# sensor_t.net
KiCad netlist of a schematic drawn in EAGLE
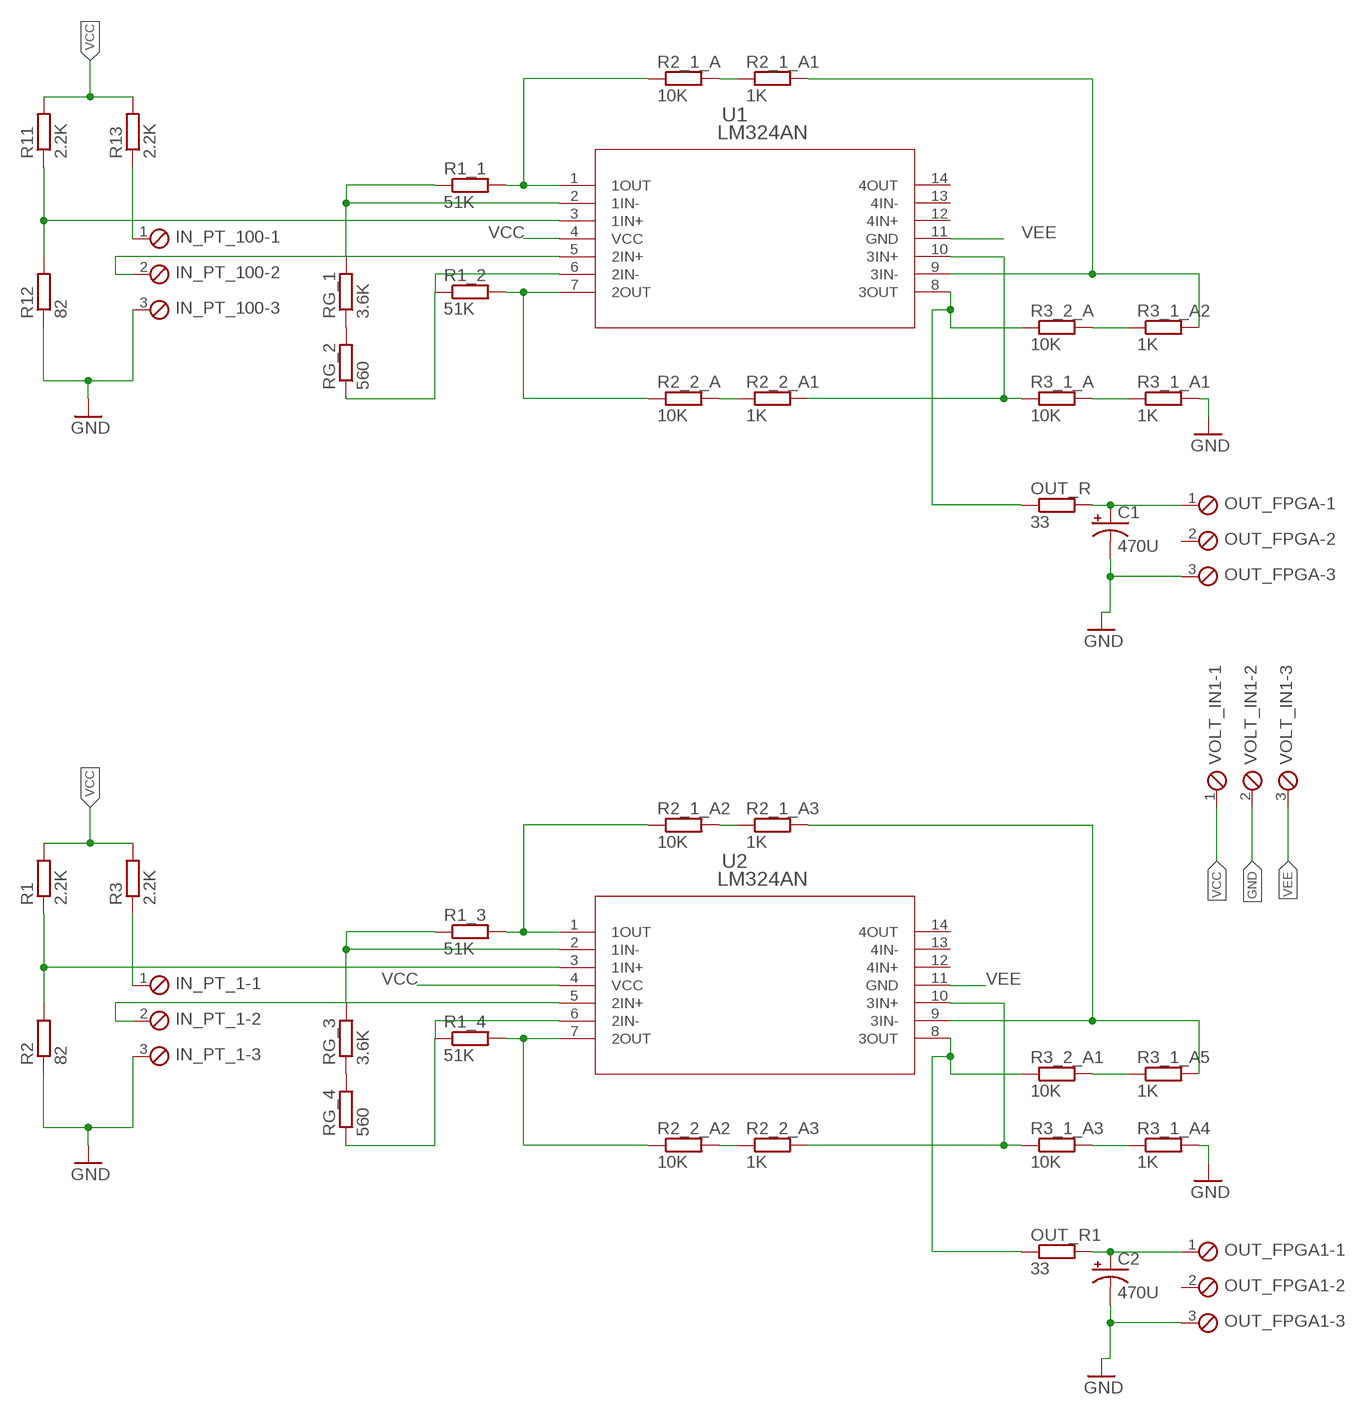
[diagram p0: schematic, sheet 1]

(export (version "E")
  (design (tool "Eeschema 10.0.6"))
  (components
    (comp (ref "C1")
      (value "470U")
      (footprint "eagle-import:TAP5-80")
      (libsource (lib "eagle-import") (part "CPOL-USTAP5-80"))
    )
    (comp (ref "C2")
      (value "470U")
      (footprint "eagle-import:TAP5-80")
      (libsource (lib "eagle-import") (part "CPOL-USTAP5-80"))
    )
    (comp (ref "IN_PT_1")
      (value "MPT3")
      (footprint "eagle-import:3POL254")
      (libsource (lib "eagle-import") (part "MPT3"))
    )
    (comp (ref "IN_PT_100")
      (value "MPT3")
      (footprint "eagle-import:3POL254")
      (libsource (lib "eagle-import") (part "MPT3"))
    )
    (comp (ref "OUT_FPGA")
      (value "MPT3")
      (footprint "eagle-import:3POL254")
      (libsource (lib "eagle-import") (part "MPT3"))
    )
    (comp (ref "OUT_FPGA1")
      (value "MPT3")
      (footprint "eagle-import:3POL254")
      (libsource (lib "eagle-import") (part "MPT3"))
    )
    (comp (ref "OUT_R")
      (value "33")
      (footprint "eagle-import:0207_10")
      (libsource (lib "eagle-import") (part "R-EU_0207/10"))
    )
    (comp (ref "OUT_R1")
      (value "33")
      (footprint "eagle-import:0207_10")
      (libsource (lib "eagle-import") (part "R-EU_0207/10"))
    )
    (comp (ref "R1")
      (value "2.2K")
      (footprint "eagle-import:0207_10")
      (libsource (lib "eagle-import") (part "R-EU_0207/10"))
    )
    (comp (ref "R1_1")
      (value "51K")
      (footprint "eagle-import:0207_10")
      (libsource (lib "eagle-import") (part "R-EU_0207/10"))
    )
    (comp (ref "R1_2")
      (value "51K")
      (footprint "eagle-import:0207_10")
      (libsource (lib "eagle-import") (part "R-EU_0207/10"))
    )
    (comp (ref "R1_3")
      (value "51K")
      (footprint "eagle-import:0207_10")
      (libsource (lib "eagle-import") (part "R-EU_0207/10"))
    )
    (comp (ref "R1_4")
      (value "51K")
      (footprint "eagle-import:0207_10")
      (libsource (lib "eagle-import") (part "R-EU_0207/10"))
    )
    (comp (ref "R2")
      (value "82")
      (footprint "eagle-import:0207_10")
      (libsource (lib "eagle-import") (part "R-EU_0207/10"))
    )
    (comp (ref "R2_1_A")
      (value "10K")
      (footprint "eagle-import:0207_10")
      (libsource (lib "eagle-import") (part "R-EU_0207/10"))
    )
    (comp (ref "R2_1_A1")
      (value "1K")
      (footprint "eagle-import:0207_10")
      (libsource (lib "eagle-import") (part "R-EU_0207/10"))
    )
    (comp (ref "R2_1_A2")
      (value "10K")
      (footprint "eagle-import:0207_10")
      (libsource (lib "eagle-import") (part "R-EU_0207/10"))
    )
    (comp (ref "R2_1_A3")
      (value "1K")
      (footprint "eagle-import:0207_10")
      (libsource (lib "eagle-import") (part "R-EU_0207/10"))
    )
    (comp (ref "R2_2_A")
      (value "10K")
      (footprint "eagle-import:0207_10")
      (libsource (lib "eagle-import") (part "R-EU_0207/10"))
    )
    (comp (ref "R2_2_A1")
      (value "1K")
      (footprint "eagle-import:0207_10")
      (libsource (lib "eagle-import") (part "R-EU_0207/10"))
    )
    (comp (ref "R2_2_A2")
      (value "10K")
      (footprint "eagle-import:0207_10")
      (libsource (lib "eagle-import") (part "R-EU_0207/10"))
    )
    (comp (ref "R2_2_A3")
      (value "1K")
      (footprint "eagle-import:0207_10")
      (libsource (lib "eagle-import") (part "R-EU_0207/10"))
    )
    (comp (ref "R3")
      (value "2.2K")
      (footprint "eagle-import:0207_10")
      (libsource (lib "eagle-import") (part "R-EU_0207/10"))
    )
    (comp (ref "R3_1_A")
      (value "10K")
      (footprint "eagle-import:0207_10")
      (libsource (lib "eagle-import") (part "R-EU_0207/10"))
    )
    (comp (ref "R3_1_A1")
      (value "1K")
      (footprint "eagle-import:0207_10")
      (libsource (lib "eagle-import") (part "R-EU_0207/10"))
    )
    (comp (ref "R3_1_A2")
      (value "1K")
      (footprint "eagle-import:0207_10")
      (libsource (lib "eagle-import") (part "R-EU_0207/10"))
    )
    (comp (ref "R3_1_A3")
      (value "10K")
      (footprint "eagle-import:0207_10")
      (libsource (lib "eagle-import") (part "R-EU_0207/10"))
    )
    (comp (ref "R3_1_A4")
      (value "1K")
      (footprint "eagle-import:0207_10")
      (libsource (lib "eagle-import") (part "R-EU_0207/10"))
    )
    (comp (ref "R3_1_A5")
      (value "1K")
      (footprint "eagle-import:0207_10")
      (libsource (lib "eagle-import") (part "R-EU_0207/10"))
    )
    (comp (ref "R3_2_A")
      (value "10K")
      (footprint "eagle-import:0207_10")
      (libsource (lib "eagle-import") (part "R-EU_0207/10"))
    )
    (comp (ref "R3_2_A1")
      (value "10K")
      (footprint "eagle-import:0207_10")
      (libsource (lib "eagle-import") (part "R-EU_0207/10"))
    )
    (comp (ref "R11")
      (value "2.2K")
      (footprint "eagle-import:0207_10")
      (libsource (lib "eagle-import") (part "R-EU_0207/10"))
    )
    (comp (ref "R12")
      (value "82")
      (footprint "eagle-import:0207_10")
      (libsource (lib "eagle-import") (part "R-EU_0207/10"))
    )
    (comp (ref "R13")
      (value "2.2K")
      (footprint "eagle-import:0207_10")
      (libsource (lib "eagle-import") (part "R-EU_0207/10"))
    )
    (comp (ref "RG_1")
      (value "3.6K")
      (footprint "eagle-import:0207_10")
      (libsource (lib "eagle-import") (part "R-EU_0207/10"))
    )
    (comp (ref "RG_2")
      (value "560")
      (footprint "eagle-import:0207_10")
      (libsource (lib "eagle-import") (part "R-EU_0207/10"))
    )
    (comp (ref "RG_3")
      (value "3.6K")
      (footprint "eagle-import:0207_10")
      (libsource (lib "eagle-import") (part "R-EU_0207/10"))
    )
    (comp (ref "RG_4")
      (value "560")
      (footprint "eagle-import:0207_10")
      (libsource (lib "eagle-import") (part "R-EU_0207/10"))
    )
    (comp (ref "U1")
      (value "LM324AN")
      (footprint "eagle-import:N14")
      (fields (field (name "COPYRIGHT") "Copyright (C) 2023 Ultra Librarian. All rights reserved."))
      (libsource (lib "eagle-import") (part "LM324AN"))
    )
    (comp (ref "U2")
      (value "LM324AN")
      (footprint "eagle-import:N14")
      (fields (field (name "COPYRIGHT") "Copyright (C) 2023 Ultra Librarian. All rights reserved."))
      (libsource (lib "eagle-import") (part "LM324AN"))
    )
    (comp (ref "VOLT_IN1")
      (value "MPT3")
      (footprint "eagle-import:3POL254")
      (libsource (lib "eagle-import") (part "MPT3"))
    )
  )
  (nets
    (net (code "1") (name "GND") (class "Default")
      (node (ref "C1") (pin "-") (pinfunction "-_-") (pintype "passive"))
      (node (ref "C2") (pin "-") (pinfunction "-_-") (pintype "passive"))
      (node (ref "IN_PT_1") (pin "3") (pinfunction "1_3") (pintype "passive"))
      (node (ref "IN_PT_100") (pin "3") (pinfunction "1_3") (pintype "passive"))
      (node (ref "OUT_FPGA") (pin "3") (pinfunction "1_3") (pintype "passive"))
      (node (ref "OUT_FPGA1") (pin "3") (pinfunction "1_3") (pintype "passive"))
      (node (ref "R12") (pin "1") (pinfunction "1_1") (pintype "passive"))
      (node (ref "R2") (pin "1") (pinfunction "1_1") (pintype "passive"))
      (node (ref "R3_1_A1") (pin "2") (pinfunction "2_2") (pintype "passive"))
      (node (ref "R3_1_A4") (pin "2") (pinfunction "2_2") (pintype "passive"))
      (node (ref "VOLT_IN1") (pin "2") (pinfunction "1_2") (pintype "passive"))
    )
    (net (code "2") (name "Net-(C1-Pad+)") (class "Default")
      (node (ref "C1") (pin "+") (pinfunction "+_+") (pintype "passive"))
      (node (ref "OUT_FPGA") (pin "1") (pinfunction "1_1") (pintype "passive"))
      (node (ref "OUT_R") (pin "2") (pinfunction "2_2") (pintype "passive"))
    )
    (net (code "3") (name "Net-(C2-Pad+)") (class "Default")
      (node (ref "C2") (pin "+") (pinfunction "+_+") (pintype "passive"))
      (node (ref "OUT_FPGA1") (pin "1") (pinfunction "1_1") (pintype "passive"))
      (node (ref "OUT_R1") (pin "2") (pinfunction "2_2") (pintype "passive"))
    )
    (net (code "4") (name "Net-(IN_PT_1-Pad1)") (class "Default")
      (node (ref "IN_PT_1") (pin "1") (pinfunction "1_1") (pintype "passive"))
      (node (ref "R3") (pin "1") (pinfunction "1_1") (pintype "passive"))
    )
    (net (code "5") (name "Net-(IN_PT_1B-1)") (class "Default")
      (node (ref "IN_PT_1") (pin "2") (pinfunction "1_2") (pintype "passive"))
      (node (ref "U2") (pin "5") (pinfunction "2IN+_5") (pintype "input"))
    )
    (net (code "6") (name "Net-(IN_PT_100-Pad1)") (class "Default")
      (node (ref "IN_PT_100") (pin "1") (pinfunction "1_1") (pintype "passive"))
      (node (ref "R13") (pin "1") (pinfunction "1_1") (pintype "passive"))
    )
    (net (code "7") (name "Net-(IN_PT_100B-1)") (class "Default")
      (node (ref "IN_PT_100") (pin "2") (pinfunction "1_2") (pintype "passive"))
      (node (ref "U1") (pin "5") (pinfunction "2IN+_5") (pintype "input"))
    )
    (net (code "8") (name "Net-(R2_1_A-Pad2)") (class "Default")
      (node (ref "R2_1_A") (pin "2") (pinfunction "2_2") (pintype "passive"))
      (node (ref "R2_1_A1") (pin "1") (pinfunction "1_1") (pintype "passive"))
    )
    (net (code "9") (name "Net-(R2_1_A2-Pad2)") (class "Default")
      (node (ref "R2_1_A2") (pin "2") (pinfunction "2_2") (pintype "passive"))
      (node (ref "R2_1_A3") (pin "1") (pinfunction "1_1") (pintype "passive"))
    )
    (net (code "10") (name "Net-(R2_2_A-Pad2)") (class "Default")
      (node (ref "R2_2_A") (pin "2") (pinfunction "2_2") (pintype "passive"))
      (node (ref "R2_2_A1") (pin "1") (pinfunction "1_1") (pintype "passive"))
    )
    (net (code "11") (name "Net-(R2_2_A2-Pad2)") (class "Default")
      (node (ref "R2_2_A2") (pin "2") (pinfunction "2_2") (pintype "passive"))
      (node (ref "R2_2_A3") (pin "1") (pinfunction "1_1") (pintype "passive"))
    )
    (net (code "12") (name "Net-(R3_1_A-Pad2)") (class "Default")
      (node (ref "R3_1_A") (pin "2") (pinfunction "2_2") (pintype "passive"))
      (node (ref "R3_1_A1") (pin "1") (pinfunction "1_1") (pintype "passive"))
    )
    (net (code "13") (name "Net-(R3_1_A2-Pad1)") (class "Default")
      (node (ref "R3_1_A2") (pin "1") (pinfunction "1_1") (pintype "passive"))
      (node (ref "R3_2_A") (pin "2") (pinfunction "2_2") (pintype "passive"))
    )
    (net (code "14") (name "Net-(R3_1_A3-Pad2)") (class "Default")
      (node (ref "R3_1_A3") (pin "2") (pinfunction "2_2") (pintype "passive"))
      (node (ref "R3_1_A4") (pin "1") (pinfunction "1_1") (pintype "passive"))
    )
    (net (code "15") (name "Net-(R3_1_A5-Pad1)") (class "Default")
      (node (ref "R3_1_A5") (pin "1") (pinfunction "1_1") (pintype "passive"))
      (node (ref "R3_2_A1") (pin "2") (pinfunction "2_2") (pintype "passive"))
    )
    (net (code "16") (name "Net-(RG_1-Pad1)") (class "Default")
      (node (ref "RG_1") (pin "1") (pinfunction "1_1") (pintype "passive"))
      (node (ref "RG_2") (pin "2") (pinfunction "2_2") (pintype "passive"))
    )
    (net (code "17") (name "Net-(RG_3-Pad1)") (class "Default")
      (node (ref "RG_3") (pin "1") (pinfunction "1_1") (pintype "passive"))
      (node (ref "RG_4") (pin "2") (pinfunction "2_2") (pintype "passive"))
    )
    (net (code "18") (name "Net-(U1-1IN+)") (class "Default")
      (node (ref "R11") (pin "1") (pinfunction "1_1") (pintype "passive"))
      (node (ref "R12") (pin "2") (pinfunction "2_2") (pintype "passive"))
      (node (ref "U1") (pin "3") (pinfunction "1IN+_3") (pintype "input"))
    )
    (net (code "19") (name "Net-(U1-1IN-)") (class "Default")
      (node (ref "R1_1") (pin "1") (pinfunction "1_1") (pintype "passive"))
      (node (ref "RG_1") (pin "2") (pinfunction "2_2") (pintype "passive"))
      (node (ref "U1") (pin "2") (pinfunction "1IN-_2") (pintype "input"))
    )
    (net (code "20") (name "Net-(U1-1OUT)") (class "Default")
      (node (ref "R1_1") (pin "2") (pinfunction "2_2") (pintype "passive"))
      (node (ref "R2_1_A") (pin "1") (pinfunction "1_1") (pintype "passive"))
      (node (ref "U1") (pin "1") (pinfunction "1OUT_1") (pintype "output"))
    )
    (net (code "21") (name "Net-(U1-2IN-)") (class "Default")
      (node (ref "R1_2") (pin "1") (pinfunction "1_1") (pintype "passive"))
      (node (ref "RG_2") (pin "1") (pinfunction "1_1") (pintype "passive"))
      (node (ref "U1") (pin "6") (pinfunction "2IN-_6") (pintype "input"))
    )
    (net (code "22") (name "Net-(U1-2OUT)") (class "Default")
      (node (ref "R1_2") (pin "2") (pinfunction "2_2") (pintype "passive"))
      (node (ref "R2_2_A") (pin "1") (pinfunction "1_1") (pintype "passive"))
      (node (ref "U1") (pin "7") (pinfunction "2OUT_7") (pintype "output"))
    )
    (net (code "23") (name "Net-(U1-3IN+)") (class "Default")
      (node (ref "R2_2_A1") (pin "2") (pinfunction "2_2") (pintype "passive"))
      (node (ref "R3_1_A") (pin "1") (pinfunction "1_1") (pintype "passive"))
      (node (ref "U1") (pin "10") (pinfunction "3IN+_10") (pintype "input"))
    )
    (net (code "24") (name "Net-(U1-3IN-)") (class "Default")
      (node (ref "R2_1_A1") (pin "2") (pinfunction "2_2") (pintype "passive"))
      (node (ref "R3_1_A2") (pin "2") (pinfunction "2_2") (pintype "passive"))
      (node (ref "U1") (pin "9") (pinfunction "3IN-_9") (pintype "input"))
    )
    (net (code "25") (name "Net-(U1-3OUT)") (class "Default")
      (node (ref "OUT_R") (pin "1") (pinfunction "1_1") (pintype "passive"))
      (node (ref "R3_2_A") (pin "1") (pinfunction "1_1") (pintype "passive"))
      (node (ref "U1") (pin "8") (pinfunction "3OUT_8") (pintype "output"))
    )
    (net (code "26") (name "Net-(U2-1IN+)") (class "Default")
      (node (ref "R1") (pin "1") (pinfunction "1_1") (pintype "passive"))
      (node (ref "R2") (pin "2") (pinfunction "2_2") (pintype "passive"))
      (node (ref "U2") (pin "3") (pinfunction "1IN+_3") (pintype "input"))
    )
    (net (code "27") (name "Net-(U2-1IN-)") (class "Default")
      (node (ref "R1_3") (pin "1") (pinfunction "1_1") (pintype "passive"))
      (node (ref "RG_3") (pin "2") (pinfunction "2_2") (pintype "passive"))
      (node (ref "U2") (pin "2") (pinfunction "1IN-_2") (pintype "input"))
    )
    (net (code "28") (name "Net-(U2-1OUT)") (class "Default")
      (node (ref "R1_3") (pin "2") (pinfunction "2_2") (pintype "passive"))
      (node (ref "R2_1_A2") (pin "1") (pinfunction "1_1") (pintype "passive"))
      (node (ref "U2") (pin "1") (pinfunction "1OUT_1") (pintype "output"))
    )
    (net (code "29") (name "Net-(U2-2IN-)") (class "Default")
      (node (ref "R1_4") (pin "1") (pinfunction "1_1") (pintype "passive"))
      (node (ref "RG_4") (pin "1") (pinfunction "1_1") (pintype "passive"))
      (node (ref "U2") (pin "6") (pinfunction "2IN-_6") (pintype "input"))
    )
    (net (code "30") (name "Net-(U2-2OUT)") (class "Default")
      (node (ref "R1_4") (pin "2") (pinfunction "2_2") (pintype "passive"))
      (node (ref "R2_2_A2") (pin "1") (pinfunction "1_1") (pintype "passive"))
      (node (ref "U2") (pin "7") (pinfunction "2OUT_7") (pintype "output"))
    )
    (net (code "31") (name "Net-(U2-3IN+)") (class "Default")
      (node (ref "R2_2_A3") (pin "2") (pinfunction "2_2") (pintype "passive"))
      (node (ref "R3_1_A3") (pin "1") (pinfunction "1_1") (pintype "passive"))
      (node (ref "U2") (pin "10") (pinfunction "3IN+_10") (pintype "input"))
    )
    (net (code "32") (name "Net-(U2-3IN-)") (class "Default")
      (node (ref "R2_1_A3") (pin "2") (pinfunction "2_2") (pintype "passive"))
      (node (ref "R3_1_A5") (pin "2") (pinfunction "2_2") (pintype "passive"))
      (node (ref "U2") (pin "9") (pinfunction "3IN-_9") (pintype "input"))
    )
    (net (code "33") (name "Net-(U2-3OUT)") (class "Default")
      (node (ref "OUT_R1") (pin "1") (pinfunction "1_1") (pintype "passive"))
      (node (ref "R3_2_A1") (pin "1") (pinfunction "1_1") (pintype "passive"))
      (node (ref "U2") (pin "8") (pinfunction "3OUT_8") (pintype "output"))
    )
    (net (code "34") (name "VCC") (class "Default")
      (node (ref "R1") (pin "2") (pinfunction "2_2") (pintype "passive"))
      (node (ref "R11") (pin "2") (pinfunction "2_2") (pintype "passive"))
      (node (ref "R13") (pin "2") (pinfunction "2_2") (pintype "passive"))
      (node (ref "R3") (pin "2") (pinfunction "2_2") (pintype "passive"))
      (node (ref "U1") (pin "4") (pinfunction "VCC_4") (pintype "power_in"))
      (node (ref "U2") (pin "4") (pinfunction "VCC_4") (pintype "power_in"))
      (node (ref "VOLT_IN1") (pin "1") (pinfunction "1_1") (pintype "passive"))
    )
    (net (code "35") (name "VEE") (class "Default")
      (node (ref "U1") (pin "11") (pinfunction "GND_11") (pintype "power_in"))
      (node (ref "U2") (pin "11") (pinfunction "GND_11") (pintype "power_in"))
      (node (ref "VOLT_IN1") (pin "3") (pinfunction "1_3") (pintype "passive"))
    )
    (net (code "36") (name "unconnected-(OUT_FPGA1B-1-Pad2)") (class "Default")
      (node (ref "OUT_FPGA1") (pin "2") (pinfunction "1_2") (pintype "passive"))
    )
    (net (code "37") (name "unconnected-(OUT_FPGAB-1-Pad2)") (class "Default")
      (node (ref "OUT_FPGA") (pin "2") (pinfunction "1_2") (pintype "passive"))
    )
    (net (code "38") (name "unconnected-(U1-4IN+-Pad12)") (class "Default")
      (node (ref "U1") (pin "12") (pinfunction "4IN+_12") (pintype "input"))
    )
    (net (code "39") (name "unconnected-(U1-4IN--Pad13)") (class "Default")
      (node (ref "U1") (pin "13") (pinfunction "4IN-_13") (pintype "input"))
    )
    (net (code "40") (name "unconnected-(U1-4OUT-Pad14)") (class "Default")
      (node (ref "U1") (pin "14") (pinfunction "4OUT_14") (pintype "output"))
    )
    (net (code "41") (name "unconnected-(U2-4IN+-Pad12)") (class "Default")
      (node (ref "U2") (pin "12") (pinfunction "4IN+_12") (pintype "input"))
    )
    (net (code "42") (name "unconnected-(U2-4IN--Pad13)") (class "Default")
      (node (ref "U2") (pin "13") (pinfunction "4IN-_13") (pintype "input"))
    )
    (net (code "43") (name "unconnected-(U2-4OUT-Pad14)") (class "Default")
      (node (ref "U2") (pin "14") (pinfunction "4OUT_14") (pintype "output"))
    )
  )
)
